# converter_schematic.net
KiCad netlist of a schematic drawn in EasyEDA
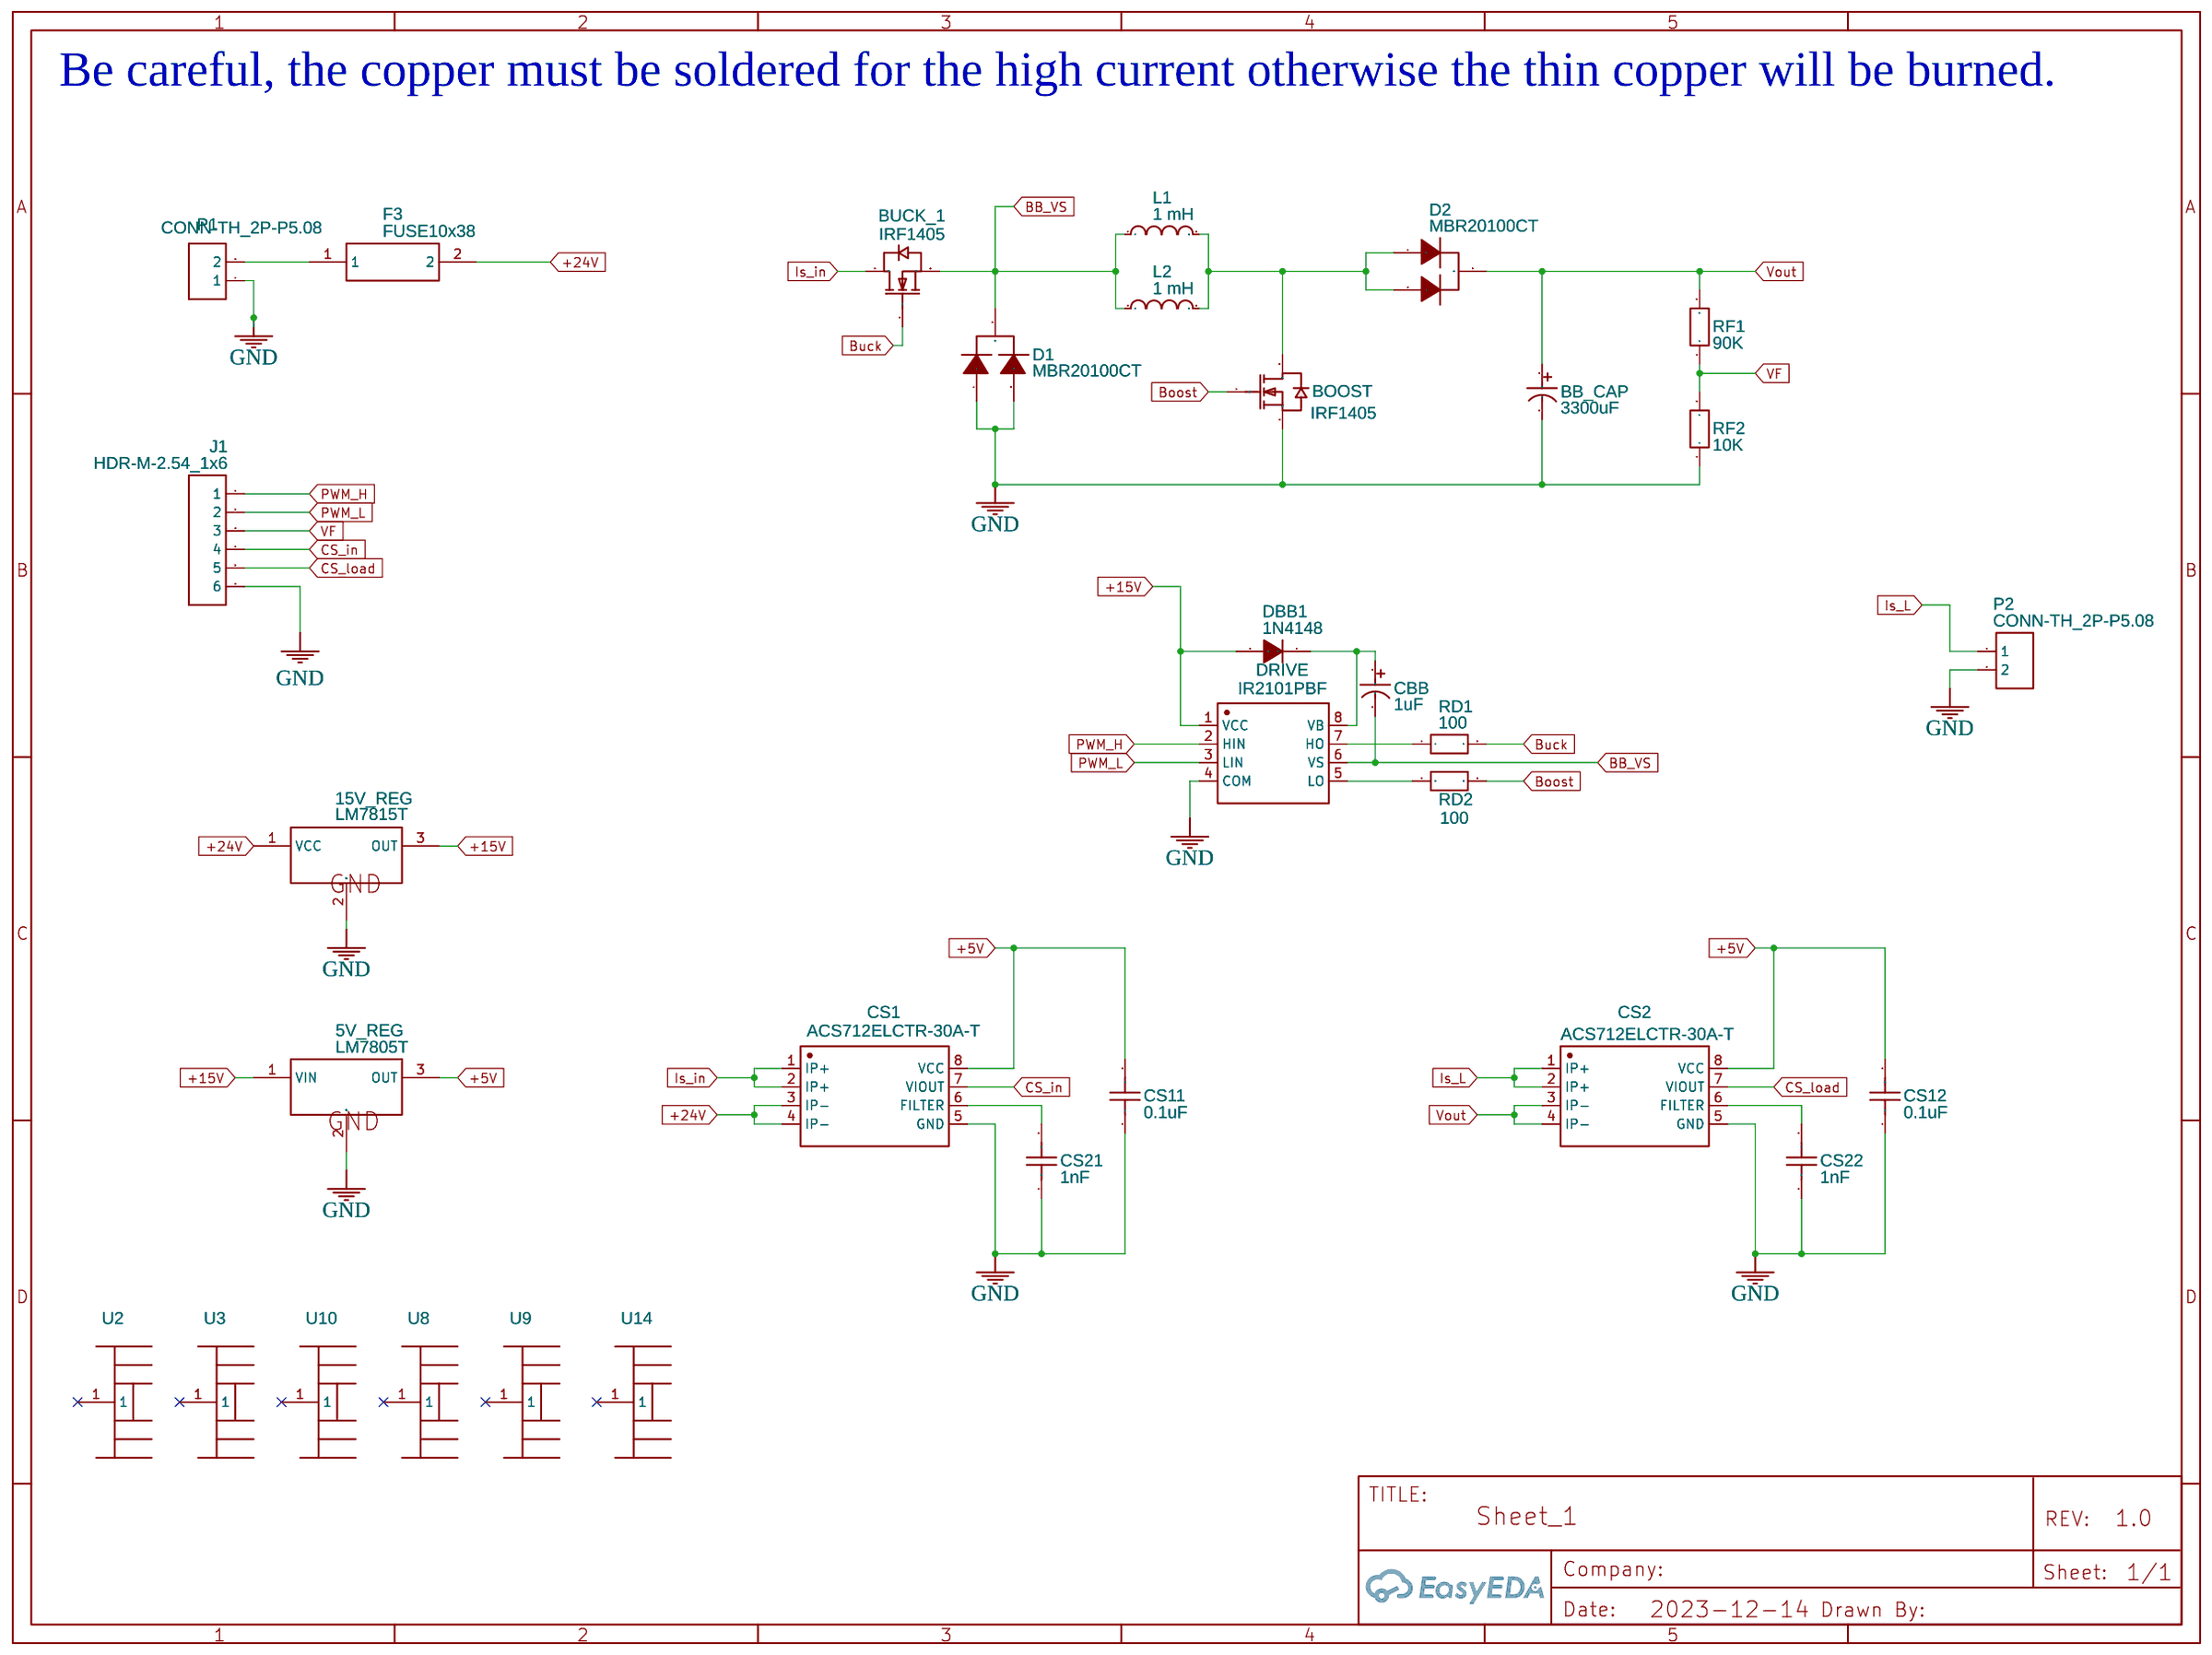
[diagram p0: schematic sheet]

(export (version "E")
  (design (tool "Eeschema 10.0.6"))
  (components
    (comp (ref "5V_REG")
      (value "LM7805T")
      (fields (field (name "Manufacturer") "HGC(华冠)"))
      (libsource (lib "") (part "LM7805T"))
    )
    (comp (ref "15V_REG")
      (value "LM7815T")
      (fields (field (name "Manufacturer") "HGSEMI(华冠)"))
      (libsource (lib "") (part "LM7815T"))
    )
    (comp (ref "BB_CAP")
      (value "3300uF")
      (fields (field (name "Manufacturer Part") "3300uF 50V 18*36") (field (name "Manufacturer") "ValuePro"))
      (libsource (lib "") (part "3300UF 50V 18*36"))
    )
    (comp (ref "BOOST")
      (value "IRF1405")
      (fields (field (name "Manufacturer Part") "IRF1405PBF-VB") (field (name "Manufacturer") "VBsemi(微碧)"))
      (libsource (lib "") (part "IRF1405PBF-VB_1"))
    )
    (comp (ref "BUCK_1")
      (value "IRF1405")
      (fields (field (name "Manufacturer Part") "IRF1405PBF-VB") (field (name "Manufacturer") "VBsemi(微碧)"))
      (libsource (lib "") (part "IRF1405PBF-VB"))
    )
    (comp (ref "CBB")
      (value "1uF")
      (fields
        (field (name "Manufacturer Part") "KF105M050C05RR0VH2FP0")
        (field (name "Manufacturer") "CX(承兴)")
      )
      (libsource (lib "") (part "1uF 50V 4*5"))
    )
    (comp (ref "CS1")
      (value "ACS712ELCTR-30A-T")
      (fields (field (name "Manufacturer") "ALLEGRO(美国埃戈罗)"))
      (libsource (lib "") (part "ACS712ELCTR-30A-T"))
    )
    (comp (ref "CS2")
      (value "ACS712ELCTR-30A-T")
      (fields (field (name "Manufacturer") "ALLEGRO(美国埃戈罗)"))
      (libsource (lib "") (part "ACS712ELCTR-30A-T"))
    )
    (comp (ref "CS11") (value "0.1uF") (libsource (lib "") (part "C_RAD-0.1_US")))
    (comp (ref "CS12") (value "0.1uF") (libsource (lib "") (part "C_RAD-0.1_US")))
    (comp (ref "CS21") (value "1nF") (libsource (lib "") (part "C_RAD-0.1_US")))
    (comp (ref "CS22") (value "1nF") (libsource (lib "") (part "C_RAD-0.1_US")))
    (comp (ref "D1")
      (value "MBR20100CT")
      (fields (field (name "Manufacturer") "minos(迈诺斯)"))
      (libsource (lib "") (part "MBR20100CT_C2920871_1"))
    )
    (comp (ref "D2")
      (value "MBR20100CT")
      (fields (field (name "Manufacturer") "minos(迈诺斯)"))
      (libsource (lib "") (part "MBR20100CT_C2920871"))
    )
    (comp (ref "DBB1")
      (value "1N4148")
      (fields (field (name "Manufacturer") "星海"))
      (libsource (lib "") (part "1N4148-C85057"))
    )
    (comp (ref "DRIVE")
      (value "IR2101PBF")
      (fields (field (name "Manufacturer") "Infineon(英飞凌)"))
      (libsource (lib "") (part "IR2101PBF"))
    )
    (comp (ref "F3") (value "FUSE10x38") (libsource (lib "") (part "FUSE10x38")))
    (comp (ref "J1") (value "HDR-M-2.54_1x6") (libsource (lib "") (part "HDR-M-2.54_1x6")))
    (comp (ref "L1") (value "1 mH") (libsource (lib "") (part "HCTI-47-10.7")))
    (comp (ref "L2") (value "1 mH") (libsource (lib "") (part "HCTI-47-10.7")))
    (comp (ref "P1") (value "CONN-TH_2P-P5.08") (libsource (lib "") (part "CONN-TH_2P-P5.08")))
    (comp (ref "P2") (value "CONN-TH_2P-P5.08") (libsource (lib "") (part "CONN-TH_2P-P5.08_1")))
    (comp (ref "RD1") (value "100") (libsource (lib "") (part "R_AXIAL-0.4_EU")))
    (comp (ref "RD2") (value "100") (libsource (lib "") (part "R_AXIAL-0.4_EU")))
    (comp (ref "RF1") (value "90K") (libsource (lib "") (part "R_AXIAL-0.4_EU_1")))
    (comp (ref "RF2") (value "10K") (libsource (lib "") (part "R_AXIAL-0.4_EU_1")))
    (comp (ref "U2")
      (value "散热片15.5*10.5*24 带针")
      (fields (field (name "Manufacturer") "XSD(鑫顺达)"))
      (libsource (lib "") (part "散热片15.5*10.5*24 带针"))
    )
    (comp (ref "U3")
      (value "散热片15.5*10.5*24 带针")
      (fields (field (name "Manufacturer") "XSD(鑫顺达)"))
      (libsource (lib "") (part "散热片15.5*10.5*24 带针"))
    )
    (comp (ref "U8")
      (value "散热片15.5*10.5*24 带针")
      (fields (field (name "Manufacturer") "XSD(鑫顺达)"))
      (libsource (lib "") (part "散热片15.5*10.5*24 带针"))
    )
    (comp (ref "U9")
      (value "散热片15.5*10.5*24 带针")
      (fields (field (name "Manufacturer") "XSD(鑫顺达)"))
      (libsource (lib "") (part "散热片15.5*10.5*24 带针"))
    )
    (comp (ref "U10")
      (value "散热片15.5*10.5*24 带针")
      (fields (field (name "Manufacturer") "XSD(鑫顺达)"))
      (libsource (lib "") (part "散热片15.5*10.5*24 带针"))
    )
    (comp (ref "U14")
      (value "散热片15.5*10.5*24 带针")
      (fields (field (name "Manufacturer") "XSD(鑫顺达)"))
      (libsource (lib "") (part "散热片15.5*10.5*24 带针"))
    )
  )
  (nets
    (net (code "1") (name "+5V") (class "Default")
      (node (ref "5V_REG") (pin "3") (pinfunction "OUT_3") (pintype "passive"))
      (node (ref "CS1") (pin "8") (pinfunction "VCC_8") (pintype "unspecified"))
      (node (ref "CS11") (pin "2") (pinfunction "2_2") (pintype "unspecified"))
      (node (ref "CS12") (pin "2") (pinfunction "2_2") (pintype "unspecified"))
      (node (ref "CS2") (pin "8") (pinfunction "VCC_8") (pintype "unspecified"))
    )
    (net (code "2") (name "+15V") (class "Default")
      (node (ref "15V_REG") (pin "3") (pinfunction "OUT_3") (pintype "passive"))
      (node (ref "5V_REG") (pin "1") (pinfunction "VIN_1") (pintype "passive"))
      (node (ref "DBB1") (pin "2") (pinfunction "A_2") (pintype "unspecified"))
      (node (ref "DRIVE") (pin "1") (pinfunction "VCC_1") (pintype "unspecified"))
    )
    (net (code "3") (name "+24V") (class "Default")
      (node (ref "15V_REG") (pin "1") (pinfunction "VCC_1") (pintype "passive"))
      (node (ref "CS1") (pin "3") (pinfunction "IP-_3") (pintype "unspecified"))
      (node (ref "CS1") (pin "4") (pinfunction "IP-_4") (pintype "unspecified"))
      (node (ref "F3") (pin "2") (pinfunction "2_2") (pintype "unspecified"))
    )
    (net (code "4") (name "BB_VS") (class "Default")
      (node (ref "BUCK_1") (pin "3") (pinfunction "S_3") (pintype "unspecified"))
      (node (ref "CBB") (pin "2") (pinfunction "2_2") (pintype "input"))
      (node (ref "D1") (pin "2") (pinfunction "C_2") (pintype "unspecified"))
      (node (ref "DRIVE") (pin "6") (pinfunction "VS_6") (pintype "unspecified"))
      (node (ref "L1") (pin "1") (pinfunction "1_1") (pintype "unspecified"))
      (node (ref "L2") (pin "1") (pinfunction "1_1") (pintype "unspecified"))
    )
    (net (code "5") (name "Boost") (class "Default")
      (node (ref "BOOST") (pin "1") (pinfunction "G_1") (pintype "unspecified"))
      (node (ref "RD2") (pin "2") (pinfunction "2_2") (pintype "unspecified"))
    )
    (net (code "6") (name "Buck") (class "Default")
      (node (ref "BUCK_1") (pin "1") (pinfunction "G_1") (pintype "unspecified"))
      (node (ref "RD1") (pin "2") (pinfunction "2_2") (pintype "unspecified"))
    )
    (net (code "7") (name "CS_in") (class "Default")
      (node (ref "CS1") (pin "7") (pinfunction "VIOUT_7") (pintype "unspecified"))
      (node (ref "J1") (pin "4") (pinfunction "4_4") (pintype "input"))
    )
    (net (code "8") (name "CS_load") (class "Default")
      (node (ref "CS2") (pin "7") (pinfunction "VIOUT_7") (pintype "unspecified"))
      (node (ref "J1") (pin "5") (pinfunction "5_5") (pintype "input"))
    )
    (net (code "9") (name "GND") (class "Default")
      (node (ref "15V_REG") (pin "2") (pinfunction "GND_2") (pintype "passive"))
      (node (ref "5V_REG") (pin "2") (pinfunction "GND_2") (pintype "passive"))
      (node (ref "BB_CAP") (pin "2") (pinfunction "2_2") (pintype "input"))
      (node (ref "BOOST") (pin "3") (pinfunction "S_3") (pintype "unspecified"))
      (node (ref "CS1") (pin "5") (pinfunction "GND_5") (pintype "unspecified"))
      (node (ref "CS11") (pin "1") (pinfunction "1_1") (pintype "unspecified"))
      (node (ref "CS12") (pin "1") (pinfunction "1_1") (pintype "unspecified"))
      (node (ref "CS2") (pin "5") (pinfunction "GND_5") (pintype "unspecified"))
      (node (ref "CS21") (pin "1") (pinfunction "1_1") (pintype "unspecified"))
      (node (ref "CS22") (pin "1") (pinfunction "1_1") (pintype "unspecified"))
      (node (ref "D1") (pin "1") (pinfunction "A_1") (pintype "unspecified"))
      (node (ref "D1") (pin "3") (pinfunction "A_3") (pintype "unspecified"))
      (node (ref "DRIVE") (pin "4") (pinfunction "COM_4") (pintype "unspecified"))
      (node (ref "J1") (pin "6") (pinfunction "6_6") (pintype "input"))
      (node (ref "P1") (pin "1") (pinfunction "1_1") (pintype "unspecified"))
      (node (ref "P2") (pin "2") (pinfunction "2_2") (pintype "unspecified"))
      (node (ref "RF2") (pin "1") (pinfunction "1_1") (pintype "unspecified"))
    )
    (net (code "10") (name "Is_L") (class "Default")
      (node (ref "CS2") (pin "1") (pinfunction "IP+_1") (pintype "unspecified"))
      (node (ref "CS2") (pin "2") (pinfunction "IP+_2") (pintype "unspecified"))
      (node (ref "P2") (pin "1") (pinfunction "1_1") (pintype "unspecified"))
    )
    (net (code "11") (name "Is_in") (class "Default")
      (node (ref "BUCK_1") (pin "2") (pinfunction "D_2") (pintype "unspecified"))
      (node (ref "CS1") (pin "1") (pinfunction "IP+_1") (pintype "unspecified"))
      (node (ref "CS1") (pin "2") (pinfunction "IP+_2") (pintype "unspecified"))
    )
    (net (code "12") (name "Net-(BOOST-D)") (class "Default")
      (node (ref "BOOST") (pin "2") (pinfunction "D_2") (pintype "unspecified"))
      (node (ref "D2") (pin "1") (pinfunction "A_1") (pintype "unspecified"))
      (node (ref "D2") (pin "3") (pinfunction "A_3") (pintype "unspecified"))
      (node (ref "L1") (pin "2") (pinfunction "2_2") (pintype "unspecified"))
      (node (ref "L2") (pin "2") (pinfunction "2_2") (pintype "unspecified"))
    )
    (net (code "13") (name "Net-(CS1-FILTER)") (class "Default")
      (node (ref "CS1") (pin "6") (pinfunction "FILTER_6") (pintype "unspecified"))
      (node (ref "CS21") (pin "2") (pinfunction "2_2") (pintype "unspecified"))
    )
    (net (code "14") (name "Net-(CS2-FILTER)") (class "Default")
      (node (ref "CS2") (pin "6") (pinfunction "FILTER_6") (pintype "unspecified"))
      (node (ref "CS22") (pin "2") (pinfunction "2_2") (pintype "unspecified"))
    )
    (net (code "15") (name "Net-(DBB1-C)") (class "Default")
      (node (ref "CBB") (pin "1") (pinfunction "1_1") (pintype "input"))
      (node (ref "DBB1") (pin "1") (pinfunction "C_1") (pintype "unspecified"))
      (node (ref "DRIVE") (pin "8") (pinfunction "VB_8") (pintype "unspecified"))
    )
    (net (code "16") (name "Net-(DRIVE-HO)") (class "Default")
      (node (ref "DRIVE") (pin "7") (pinfunction "HO_7") (pintype "unspecified"))
      (node (ref "RD1") (pin "1") (pinfunction "1_1") (pintype "unspecified"))
    )
    (net (code "17") (name "Net-(DRIVE-LO)") (class "Default")
      (node (ref "DRIVE") (pin "5") (pinfunction "LO_5") (pintype "unspecified"))
      (node (ref "RD2") (pin "1") (pinfunction "1_1") (pintype "unspecified"))
    )
    (net (code "18") (name "Net-(F3-Pad1)") (class "Default")
      (node (ref "F3") (pin "1") (pinfunction "1_1") (pintype "unspecified"))
      (node (ref "P1") (pin "2") (pinfunction "2_2") (pintype "unspecified"))
    )
    (net (code "19") (name "PWM_H") (class "Default")
      (node (ref "DRIVE") (pin "2") (pinfunction "HIN_2") (pintype "unspecified"))
      (node (ref "J1") (pin "1") (pinfunction "1_1") (pintype "input"))
    )
    (net (code "20") (name "PWM_L") (class "Default")
      (node (ref "DRIVE") (pin "3") (pinfunction "LIN_3") (pintype "unspecified"))
      (node (ref "J1") (pin "2") (pinfunction "2_2") (pintype "input"))
    )
    (net (code "21") (name "VF") (class "Default")
      (node (ref "J1") (pin "3") (pinfunction "3_3") (pintype "input"))
      (node (ref "RF1") (pin "1") (pinfunction "1_1") (pintype "unspecified"))
      (node (ref "RF2") (pin "2") (pinfunction "2_2") (pintype "unspecified"))
    )
    (net (code "22") (name "Vout") (class "Default")
      (node (ref "BB_CAP") (pin "1") (pinfunction "1_1") (pintype "input"))
      (node (ref "CS2") (pin "3") (pinfunction "IP-_3") (pintype "unspecified"))
      (node (ref "CS2") (pin "4") (pinfunction "IP-_4") (pintype "unspecified"))
      (node (ref "D2") (pin "2") (pinfunction "C_2") (pintype "unspecified"))
      (node (ref "RF1") (pin "2") (pinfunction "2_2") (pintype "unspecified"))
    )
    (net (code "23") (name "unconnected-(U2-Pad1)") (class "Default")
      (node (ref "U2") (pin "1") (pinfunction "1_1") (pintype "unspecified+no_connect"))
    )
    (net (code "24") (name "unconnected-(U3-Pad1)") (class "Default")
      (node (ref "U3") (pin "1") (pinfunction "1_1") (pintype "unspecified+no_connect"))
    )
    (net (code "25") (name "unconnected-(U8-Pad1)") (class "Default")
      (node (ref "U8") (pin "1") (pinfunction "1_1") (pintype "unspecified+no_connect"))
    )
    (net (code "26") (name "unconnected-(U9-Pad1)") (class "Default")
      (node (ref "U9") (pin "1") (pinfunction "1_1") (pintype "unspecified+no_connect"))
    )
    (net (code "27") (name "unconnected-(U10-Pad1)") (class "Default")
      (node (ref "U10") (pin "1") (pinfunction "1_1") (pintype "unspecified+no_connect"))
    )
    (net (code "28") (name "unconnected-(U14-Pad1)") (class "Default")
      (node (ref "U14") (pin "1") (pinfunction "1_1") (pintype "unspecified+no_connect"))
    )
  )
)
